# Digital_clock_schematic.net
KiCad netlist of a schematic drawn in Altium Designer
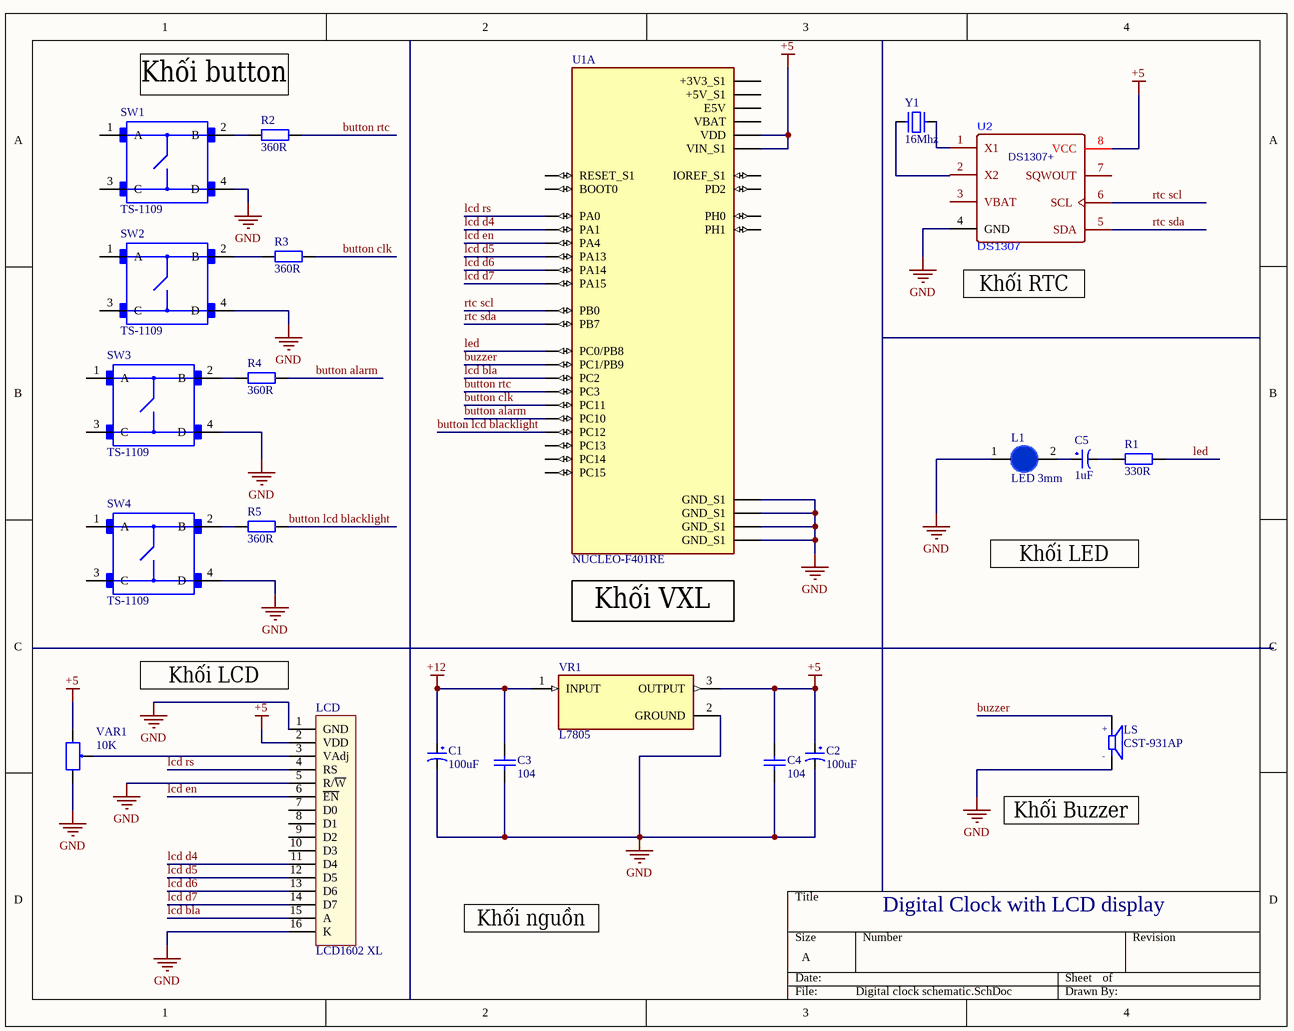
[diagram p0: Digital clock schematic.SchDoc]

(export (version "E")
  (design (tool "Eeschema 10.0.6"))
  (components
    (comp (ref "C1")
      (value "100uF")
      (footprint "tu hoa 5mm")
      (description "Cắm")
      (libsource (lib "Altium_Lib_by_KhueNguyenCreator") (part "Tu Hoa 100uF 25V 6x11"))
    )
    (comp (ref "C2")
      (value "100uF")
      (footprint "tu hoa 5mm")
      (description "Cắm")
      (libsource (lib "Altium_Lib_by_KhueNguyenCreator") (part "Tu Hoa 100uF 16V 5x7"))
    )
    (comp (ref "C3")
      (value "104")
      (footprint "tu 0603")
      (description "Dán")
      (libsource (lib "Altium_Lib_by_KhueNguyenCreator") (part "Tu 0603 104 50V 10%"))
    )
    (comp (ref "C4")
      (value "104")
      (footprint "tu 0603")
      (description "Dán")
      (libsource (lib "Altium_Lib_by_KhueNguyenCreator") (part "Tu 0603 104 50V 10%"))
    )
    (comp (ref "C5")
      (value "1uF")
      (footprint "tu hoa 5mm")
      (description "Cắm")
      (libsource (lib "Altium_Lib_by_KhueNguyenCreator") (part "Tu Hoa 1uF 400V 6x10"))
    )
    (comp (ref "L1")
      (value "LED 3mm")
      (footprint "LED-3MM-BLUE")
      (description "Cắm")
      (libsource (lib "Altium_Lib_by_KhueNguyenCreator") (part "LED 3mm Xanh Duong"))
    )
    (comp (ref "LCD")
      (value "LCD1602 XL")
      (footprint "LCD1602 with Jump")
      (description "LCD 1602 Xanh Lá")
      (libsource (lib "Altium_Lib_by_KhueNguyenCreator") (part "LCD1602 XL"))
    )
    (comp (ref "LS")
      (value "CST-931AP")
      (footprint "CUI_CST-931AP")
      (description "9 mm, 3 V, 85 dB, Through Hole, Magnetic Audio Transducer Buzzer")
      (fields (field (name "MF") "CUI Devices"))
      (libsource (lib "CST-931AP") (part "CST-931AP"))
    )
    (comp (ref "R1")
      (value "330R")
      (footprint "tro vach 1/4w")
      (description "Cắm")
      (libsource (lib "Altium_Lib_by_KhueNguyenCreator") (part "Tro Vach 1/4W 1% 330R"))
    )
    (comp (ref "R2")
      (value "360R")
      (footprint "tro vach 1/4w")
      (description "Cắm")
      (libsource (lib "Altium_Lib_by_KhueNguyenCreator") (part "Tro Vach 1/4W 1% 360R"))
    )
    (comp (ref "R3")
      (value "360R")
      (footprint "tro vach 1/4w")
      (description "Cắm")
      (libsource (lib "Altium_Lib_by_KhueNguyenCreator") (part "Tro Vach 1/4W 1% 360R"))
    )
    (comp (ref "R4")
      (value "360R")
      (footprint "tro vach 1/4w")
      (description "Cắm")
      (libsource (lib "Altium_Lib_by_KhueNguyenCreator") (part "Tro Vach 1/4W 1% 360R"))
    )
    (comp (ref "R5")
      (value "360R")
      (footprint "tro vach 1/4w")
      (description "Cắm")
      (libsource (lib "Altium_Lib_by_KhueNguyenCreator") (part "Tro Vach 1/4W 1% 360R"))
    )
    (comp (ref "SW1")
      (value "TS-1109")
      (footprint "SW_TS-1109")
      (description "Heat Sink Full Brick DC/DC Converter Aluminum Top Mount")
      (fields (field (name "MF") "Samtec Inc."))
      (libsource (lib "TS-1109") (part "TS-1109"))
    )
    (comp (ref "SW2")
      (value "TS-1109")
      (footprint "SW_TS-1109")
      (description "Heat Sink Full Brick DC/DC Converter Aluminum Top Mount")
      (fields (field (name "MF") "Samtec Inc."))
      (libsource (lib "TS-1109") (part "TS-1109"))
    )
    (comp (ref "SW3")
      (value "TS-1109")
      (footprint "SW_TS-1109")
      (description "Heat Sink Full Brick DC/DC Converter Aluminum Top Mount")
      (fields (field (name "MF") "Samtec Inc."))
      (libsource (lib "TS-1109") (part "TS-1109"))
    )
    (comp (ref "SW4")
      (value "TS-1109")
      (footprint "SW_TS-1109")
      (description "Heat Sink Full Brick DC/DC Converter Aluminum Top Mount")
      (fields (field (name "MF") "Samtec Inc."))
      (libsource (lib "TS-1109") (part "TS-1109"))
    )
    (comp (ref "U1")
      (value "NUCLEO-F401RE")
      (footprint "ST_NUCLEO-F401RE")
      (libsource (lib "NUCLEO-F401RE (1)") (part "NUCLEO-F401RE"))
    )
    (comp (ref "U2")
      (value "DS1307")
      (footprint "SOP 8")
      (description "C5145427")
      (libsource (lib "Altium_Lib_by_KhueNguyenCreator") (part "DS1307"))
    )
    (comp (ref "VAR1")
      (value "10K")
      (footprint "BIEN TRO VI CHINH NAM")
      (description "Cắm")
      (libsource (lib "Altium_Lib_by_KhueNguyenCreator") (part "Bien Tro Tinh Chinh 100R Nam"))
    )
    (comp (ref "VR1")
      (value "L7805")
      (footprint "TO255P1020X450X2000-3")
      (description "Standard Regulator Pos 5V 1.5A 3-Pin(3+Tab) TO-220FP Tube")
      (fields (field (name "MF") "STMicroelectronics"))
      (libsource (lib "L7805") (part "L7805"))
    )
    (comp (ref "Y1")
      (value "16Mhz")
      (footprint "Thach Anh 2 Chan 32,768 KHz")
      (description "Crystal For all Crystal 2pin.")
      (libsource (lib "Altium_Lib_by_KhueNguyenCreator") (part "Thach Anh 2 chan 32,768 Khz"))
    )
  )
  (nets
    (net (code "1") (name "+5") (class "Default")
      (node (ref "C2") (pin "1") (pinfunction "1_1") (pintype "passive"))
      (node (ref "C4") (pin "2") (pinfunction "2_2") (pintype "passive"))
      (node (ref "LCD") (pin "2") (pinfunction "VDD_2") (pintype "passive"))
      (node (ref "U1") (pin "CN7_24") (pinfunction "VIN_S1_CN7_24") (pintype "power_in"))
      (node (ref "U1") (pin "CN7_5") (pinfunction "VDD_CN7_5") (pintype "power_in"))
      (node (ref "U2") (pin "8") (pinfunction "VCC_8") (pintype "passive"))
      (node (ref "VAR1") (pin "1") (pinfunction "1_1") (pintype "passive"))
      (node (ref "VR1") (pin "3") (pinfunction "OUTPUT_3") (pintype "output"))
    )
    (net (code "2") (name "+12") (class "Default")
      (node (ref "C1") (pin "1") (pinfunction "1_1") (pintype "passive"))
      (node (ref "C3") (pin "2") (pinfunction "2_2") (pintype "passive"))
      (node (ref "VR1") (pin "1") (pinfunction "INPUT_1") (pintype "input"))
    )
    (net (code "3") (name "/button alarm") (class "Default")
      (node (ref "R4") (pin "2") (pinfunction "2_2") (pintype "passive"))
      (node (ref "U1") (pin "CN7_1") (pinfunction "PC10_CN7_1") (pintype "bidirectional"))
    )
    (net (code "4") (name "/button clk") (class "Default")
      (node (ref "R3") (pin "2") (pinfunction "2_2") (pintype "passive"))
      (node (ref "U1") (pin "CN7_2") (pinfunction "PC11_CN7_2") (pintype "bidirectional"))
    )
    (net (code "5") (name "/button lcd blacklight") (class "Default")
      (node (ref "R5") (pin "2") (pinfunction "2_2") (pintype "passive"))
      (node (ref "U1") (pin "CN7_3") (pinfunction "PC12_CN7_3") (pintype "bidirectional"))
    )
    (net (code "6") (name "/button rtc") (class "Default")
      (node (ref "R2") (pin "2") (pinfunction "2_2") (pintype "passive"))
      (node (ref "U1") (pin "CN7_37") (pinfunction "PC3_CN7_37") (pintype "bidirectional"))
    )
    (net (code "7") (name "/buzzer") (class "Default")
      (node (ref "LS") (pin "P") (pinfunction "P_P") (pintype "passive"))
      (node (ref "U1") (pin "CN7_36") (pinfunction "PC1/PB9_CN7_36") (pintype "bidirectional"))
    )
    (net (code "8") (name "/lcd bla") (class "Default")
      (node (ref "LCD") (pin "15") (pinfunction "A_15") (pintype "passive"))
      (node (ref "U1") (pin "CN7_35") (pinfunction "PC2_CN7_35") (pintype "bidirectional"))
    )
    (net (code "9") (name "/lcd d4") (class "Default")
      (node (ref "LCD") (pin "11") (pinfunction "D4_11") (pintype "passive"))
      (node (ref "U1") (pin "CN7_30") (pinfunction "PA1_CN7_30") (pintype "bidirectional"))
    )
    (net (code "10") (name "/lcd d5") (class "Default")
      (node (ref "LCD") (pin "12") (pinfunction "D5_12") (pintype "passive"))
      (node (ref "U1") (pin "CN7_13") (pinfunction "PA13_CN7_13") (pintype "bidirectional"))
    )
    (net (code "11") (name "/lcd d6") (class "Default")
      (node (ref "LCD") (pin "13") (pinfunction "D6_13") (pintype "passive"))
      (node (ref "U1") (pin "CN7_15") (pinfunction "PA14_CN7_15") (pintype "bidirectional"))
    )
    (net (code "12") (name "/lcd d7") (class "Default")
      (node (ref "LCD") (pin "14") (pinfunction "D7_14") (pintype "passive"))
      (node (ref "U1") (pin "CN7_17") (pinfunction "PA15_CN7_17") (pintype "bidirectional"))
    )
    (net (code "13") (name "/lcd en") (class "Default")
      (node (ref "LCD") (pin "6") (pinfunction "~{EN}_6") (pintype "passive"))
      (node (ref "U1") (pin "CN7_32") (pinfunction "PA4_CN7_32") (pintype "bidirectional"))
    )
    (net (code "14") (name "/lcd rs") (class "Default")
      (node (ref "LCD") (pin "4") (pinfunction "RS_4") (pintype "passive"))
      (node (ref "U1") (pin "CN7_28") (pinfunction "PA0_CN7_28") (pintype "bidirectional"))
    )
    (net (code "15") (name "/led") (class "Default")
      (node (ref "R1") (pin "2") (pinfunction "2_2") (pintype "passive"))
      (node (ref "U1") (pin "CN7_38") (pinfunction "PC0/PB8_CN7_38") (pintype "bidirectional"))
    )
    (net (code "16") (name "/rtc scl") (class "Default")
      (node (ref "U1") (pin "CN7_34") (pinfunction "PB0_CN7_34") (pintype "bidirectional"))
      (node (ref "U2") (pin "6") (pinfunction "SCL_6") (pintype "passive"))
    )
    (net (code "17") (name "/rtc sda") (class "Default")
      (node (ref "U1") (pin "CN7_21") (pinfunction "PB7_CN7_21") (pintype "bidirectional"))
      (node (ref "U2") (pin "5") (pinfunction "SDA_5") (pintype "passive"))
    )
    (net (code "18") (name "GND") (class "Default")
      (node (ref "C1") (pin "2") (pinfunction "2_2") (pintype "passive"))
      (node (ref "C2") (pin "2") (pinfunction "2_2") (pintype "passive"))
      (node (ref "C3") (pin "1") (pinfunction "1_1") (pintype "passive"))
      (node (ref "C4") (pin "1") (pinfunction "1_1") (pintype "passive"))
      (node (ref "L1") (pin "1") (pinfunction "A_1") (pintype "passive"))
      (node (ref "LCD") (pin "1") (pinfunction "GND_1") (pintype "passive"))
      (node (ref "LCD") (pin "16") (pinfunction "K_16") (pintype "passive"))
      (node (ref "LCD") (pin "5") (pinfunction "R/~{W}_5") (pintype "passive"))
      (node (ref "LS") (pin "M") (pinfunction "M_M") (pintype "passive"))
      (node (ref "SW1") (pin "4") (pinfunction "D_4") (pintype "passive"))
      (node (ref "SW2") (pin "4") (pinfunction "D_4") (pintype "passive"))
      (node (ref "SW3") (pin "4") (pinfunction "D_4") (pintype "passive"))
      (node (ref "SW4") (pin "4") (pinfunction "D_4") (pintype "passive"))
      (node (ref "U1") (pin "CN7_19") (pinfunction "GND_S1_CN7_19") (pintype "power_in"))
      (node (ref "U1") (pin "CN7_20") (pinfunction "GND_S1_CN7_20") (pintype "power_in"))
      (node (ref "U1") (pin "CN7_22") (pinfunction "GND_S1_CN7_22") (pintype "power_in"))
      (node (ref "U1") (pin "CN7_8") (pinfunction "GND_S1_CN7_8") (pintype "power_in"))
      (node (ref "U2") (pin "4") (pinfunction "GND_4") (pintype "passive"))
      (node (ref "VAR1") (pin "3") (pinfunction "3_3") (pintype "passive"))
      (node (ref "VR1") (pin "2") (pinfunction "GROUND_2") (pintype "power_in"))
    )
    (net (code "19") (name "Net-(C5-Pad2)") (class "Default")
      (node (ref "C5") (pin "2") (pinfunction "2_2") (pintype "passive"))
      (node (ref "R1") (pin "1") (pinfunction "1_1") (pintype "passive"))
    )
    (net (code "20") (name "Net-(L1-K)") (class "Default")
      (node (ref "C5") (pin "1") (pinfunction "1_1") (pintype "passive"))
      (node (ref "L1") (pin "2") (pinfunction "K_2") (pintype "passive"))
    )
    (net (code "21") (name "Net-(LCD-VAdj)") (class "Default")
      (node (ref "LCD") (pin "3") (pinfunction "VAdj_3") (pintype "passive"))
      (node (ref "VAR1") (pin "2") (pinfunction "2_2") (pintype "passive"))
    )
    (net (code "22") (name "Net-(SW1-B)") (class "Default")
      (node (ref "R2") (pin "1") (pinfunction "1_1") (pintype "passive"))
      (node (ref "SW1") (pin "2") (pinfunction "B_2") (pintype "passive"))
    )
    (net (code "23") (name "Net-(SW2-B)") (class "Default")
      (node (ref "R3") (pin "1") (pinfunction "1_1") (pintype "passive"))
      (node (ref "SW2") (pin "2") (pinfunction "B_2") (pintype "passive"))
    )
    (net (code "24") (name "Net-(SW3-B)") (class "Default")
      (node (ref "R4") (pin "1") (pinfunction "1_1") (pintype "passive"))
      (node (ref "SW3") (pin "2") (pinfunction "B_2") (pintype "passive"))
    )
    (net (code "25") (name "Net-(SW4-B)") (class "Default")
      (node (ref "R5") (pin "1") (pinfunction "1_1") (pintype "passive"))
      (node (ref "SW4") (pin "2") (pinfunction "B_2") (pintype "passive"))
    )
    (net (code "26") (name "Net-(U2-X1)") (class "Default")
      (node (ref "U2") (pin "1") (pinfunction "X1_1") (pintype "passive"))
      (node (ref "Y1") (pin "2") (pinfunction "2_2") (pintype "passive"))
    )
    (net (code "27") (name "unconnected-(LCD-D0-Pad7)") (class "Default")
      (node (ref "LCD") (pin "7") (pinfunction "D0_7") (pintype "passive"))
    )
    (net (code "28") (name "unconnected-(LCD-D1-Pad8)") (class "Default")
      (node (ref "LCD") (pin "8") (pinfunction "D1_8") (pintype "passive"))
    )
    (net (code "29") (name "unconnected-(LCD-D2-Pad9)") (class "Default")
      (node (ref "LCD") (pin "9") (pinfunction "D2_9") (pintype "passive"))
    )
    (net (code "30") (name "unconnected-(LCD-D3-Pad10)") (class "Default")
      (node (ref "LCD") (pin "10") (pinfunction "D3_10") (pintype "passive"))
    )
    (net (code "31") (name "unconnected-(SW1-A-Pad1)") (class "Default")
      (node (ref "SW1") (pin "1") (pinfunction "A_1") (pintype "passive"))
    )
    (net (code "32") (name "unconnected-(SW1-C-Pad3)") (class "Default")
      (node (ref "SW1") (pin "3") (pinfunction "C_3") (pintype "passive"))
    )
    (net (code "33") (name "unconnected-(SW2-A-Pad1)") (class "Default")
      (node (ref "SW2") (pin "1") (pinfunction "A_1") (pintype "passive"))
    )
    (net (code "34") (name "unconnected-(SW2-C-Pad3)") (class "Default")
      (node (ref "SW2") (pin "3") (pinfunction "C_3") (pintype "passive"))
    )
    (net (code "35") (name "unconnected-(SW3-A-Pad1)") (class "Default")
      (node (ref "SW3") (pin "1") (pinfunction "A_1") (pintype "passive"))
    )
    (net (code "36") (name "unconnected-(SW3-C-Pad3)") (class "Default")
      (node (ref "SW3") (pin "3") (pinfunction "C_3") (pintype "passive"))
    )
    (net (code "37") (name "unconnected-(SW4-A-Pad1)") (class "Default")
      (node (ref "SW4") (pin "1") (pinfunction "A_1") (pintype "passive"))
    )
    (net (code "38") (name "unconnected-(SW4-C-Pad3)") (class "Default")
      (node (ref "SW4") (pin "3") (pinfunction "C_3") (pintype "passive"))
    )
    (net (code "39") (name "unconnected-(U1A-+3V3_S1-PadCN7_16)") (class "Default")
      (node (ref "U1") (pin "CN7_16") (pinfunction "+3V3_S1_CN7_16") (pintype "power_in"))
    )
    (net (code "40") (name "unconnected-(U1A-+5V_S1-PadCN7_18)") (class "Default")
      (node (ref "U1") (pin "CN7_18") (pinfunction "+5V_S1_CN7_18") (pintype "power_in"))
    )
    (net (code "41") (name "unconnected-(U1A-BOOT0-PadCN7_7)") (class "Default")
      (node (ref "U1") (pin "CN7_7") (pinfunction "BOOT0_CN7_7") (pintype "bidirectional"))
    )
    (net (code "42") (name "unconnected-(U1A-E5V-PadCN7_6)") (class "Default")
      (node (ref "U1") (pin "CN7_6") (pinfunction "E5V_CN7_6") (pintype "power_in"))
    )
    (net (code "43") (name "unconnected-(U1A-IOREF_S1-PadCN7_12)") (class "Default")
      (node (ref "U1") (pin "CN7_12") (pinfunction "IOREF_S1_CN7_12") (pintype "bidirectional"))
    )
    (net (code "44") (name "unconnected-(U1A-PC13-PadCN7_23)") (class "Default")
      (node (ref "U1") (pin "CN7_23") (pinfunction "PC13_CN7_23") (pintype "bidirectional"))
    )
    (net (code "45") (name "unconnected-(U1A-PC14-PadCN7_25)") (class "Default")
      (node (ref "U1") (pin "CN7_25") (pinfunction "PC14_CN7_25") (pintype "bidirectional"))
    )
    (net (code "46") (name "unconnected-(U1A-PC15-PadCN7_27)") (class "Default")
      (node (ref "U1") (pin "CN7_27") (pinfunction "PC15_CN7_27") (pintype "bidirectional"))
    )
    (net (code "47") (name "unconnected-(U1A-PD2-PadCN7_4)") (class "Default")
      (node (ref "U1") (pin "CN7_4") (pinfunction "PD2_CN7_4") (pintype "bidirectional"))
    )
    (net (code "48") (name "unconnected-(U1A-PH0-PadCN7_29)") (class "Default")
      (node (ref "U1") (pin "CN7_29") (pinfunction "PH0_CN7_29") (pintype "bidirectional"))
    )
    (net (code "49") (name "unconnected-(U1A-PH1-PadCN7_31)") (class "Default")
      (node (ref "U1") (pin "CN7_31") (pinfunction "PH1_CN7_31") (pintype "bidirectional"))
    )
    (net (code "50") (name "unconnected-(U1A-RESET_S1-PadCN7_14)") (class "Default")
      (node (ref "U1") (pin "CN7_14") (pinfunction "RESET_S1_CN7_14") (pintype "bidirectional"))
    )
    (net (code "51") (name "unconnected-(U1A-VBAT-PadCN7_33)") (class "Default")
      (node (ref "U1") (pin "CN7_33") (pinfunction "VBAT_CN7_33") (pintype "power_in"))
    )
    (net (code "52") (name "unconnected-(U2-SQWOUT-Pad7)") (class "Default")
      (node (ref "U2") (pin "7") (pinfunction "SQWOUT_7") (pintype "passive"))
    )
    (net (code "53") (name "unconnected-(U2-VBAT-Pad3)") (class "Default")
      (node (ref "U2") (pin "3") (pinfunction "VBAT_3") (pintype "passive"))
    )
    (net (code "54") (name "unconnected-(U2-X2-Pad2)") (class "Default")
      (node (ref "U2") (pin "2") (pinfunction "X2_2") (pintype "passive"))
    )
    (net (code "55") (name "unconnected-(Y1-Pad1)") (class "Default")
      (node (ref "Y1") (pin "1") (pinfunction "1_1") (pintype "passive"))
    )
  )
)
